# Power_USB.net
KiCad netlist of a schematic drawn in Altium Designer
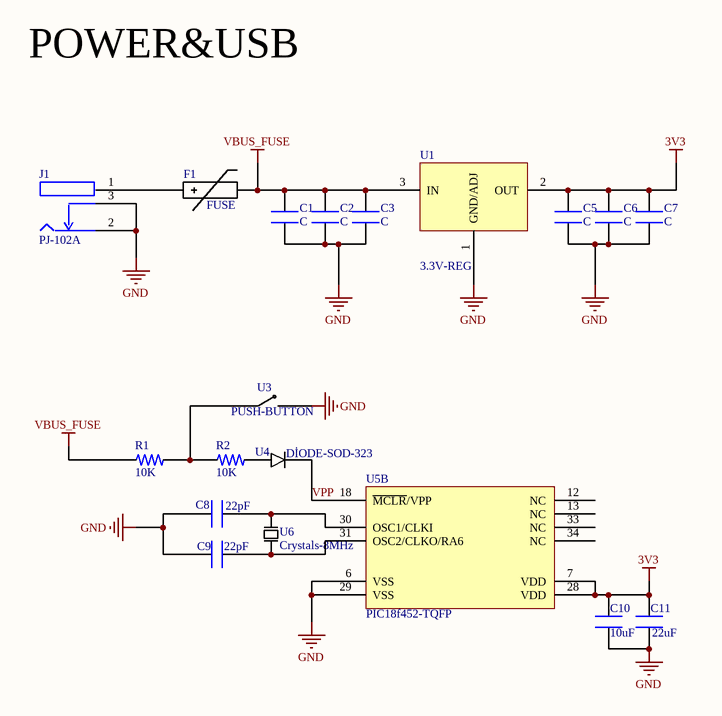
[diagram p0: Power&USB.SchDoc]

(export (version "E")
  (design (tool "Eeschema 10.0.6"))
  (components
    (comp (ref "C1")
      (value "C")
      (footprint "capacitor-1206:PCBComponent_1")
      (libsource (lib "capacitor-1206") (part "1206-CAPACİTOR"))
    )
    (comp (ref "C2")
      (value "C")
      (footprint "capacitor-1206:PCBComponent_1")
      (libsource (lib "capacitor-1206") (part "1206-CAPACİTOR"))
    )
    (comp (ref "C3")
      (value "C")
      (footprint "capacitor-1206:PCBComponent_1")
      (libsource (lib "capacitor-1206") (part "1206-CAPACİTOR"))
    )
    (comp (ref "C5")
      (value "C")
      (footprint "capacitor-1206:PCBComponent_1")
      (libsource (lib "capacitor-1206") (part "1206-CAPACİTOR"))
    )
    (comp (ref "C6")
      (value "C")
      (footprint "capacitor-1206:PCBComponent_1")
      (libsource (lib "capacitor-1206") (part "1206-CAPACİTOR"))
    )
    (comp (ref "C7")
      (value "C")
      (footprint "capacitor-1206:PCBComponent_1")
      (libsource (lib "capacitor-1206") (part "1206-CAPACİTOR"))
    )
    (comp (ref "C8")
      (value "22pF")
      (footprint "capacitor-1206:PCBComponent_1")
      (libsource (lib "capacitor-1206") (part "1206-CAPACİTOR"))
    )
    (comp (ref "C9")
      (value "22pF")
      (footprint "capacitor-1206:PCBComponent_1")
      (libsource (lib "capacitor-1206") (part "1206-CAPACİTOR"))
    )
    (comp (ref "C10")
      (value "10uF")
      (footprint "capacitor-1206:PCBComponent_1")
      (libsource (lib "capacitor-1206") (part "1206-CAPACİTOR"))
    )
    (comp (ref "C11")
      (value "22uF")
      (footprint "capacitor-1206:PCBComponent_1")
      (libsource (lib "capacitor-1206") (part "1206-CAPACİTOR"))
    )
    (comp (ref "F1")
      (value "FUSE")
      (footprint "Fuse-0805:PCBComponent_1")
      (libsource (lib "Fuse-0805") (part "Component_1"))
    )
    (comp (ref "J1")
      (value "PJ-102A")
      (footprint "FP-PJ-102A-MFG")
      (description "CONN PWR JACK 2X5.5MM SOLDER")
      (fields (field (name "MANUFACTURER") "CUI") (field (name "VOLTAGE") "24V"))
      (libsource (lib "Altium Content Vault") (part "0685d7ee7311ef3291d1b1b03391b7d"))
    )
    (comp (ref "R1")
      (value "10K")
      (footprint "1206-Resistor:PCBComponent_1")
      (libsource (lib "1206-Resistor") (part "1206-RESİSTOR"))
    )
    (comp (ref "R2")
      (value "10K")
      (footprint "1206-Resistor:PCBComponent_1")
      (libsource (lib "1206-Resistor") (part "1206-RESİSTOR"))
    )
    (comp (ref "U1")
      (value "3.3V-REG")
      (footprint "3.3V-VOLTAGEREG:PCBComponent_1")
      (libsource (lib "3.3V-VOLTAGEREG") (part "LD1117AG-33-AA3-A-R"))
    )
    (comp (ref "U3")
      (value "PUSH-BUTTON")
      (footprint "Button:PCBComponent_1")
      (libsource (lib "Button") (part "DS1042-03-2-1-KKA-160-10"))
    )
    (comp (ref "U4")
      (value "DİODE-SOD-323")
      (footprint "DİODE-SOD-323:PCBComponent_1")
      (libsource (lib "Diode-SOD-323") (part "1N4148WS-HT"))
    )
    (comp (ref "U5")
      (value "PIC18f452-TQFP")
      (footprint "pic16f1937:PCBComponent_1")
      (libsource (lib "dspic30f2023") (part "PIC18f452-TQFP"))
    )
    (comp (ref "U6")
      (value "Crystals-8MHz")
      (footprint "Crystals-8MHz:PCBComponent_1")
      (libsource (lib "Crystals-8MHz") (part "Crystals-8MHz-SMD"))
    )
  )
  (nets
    (net (code "1") (name "/VPP") (class "Default")
      (node (ref "U4") (pin "2") (pintype "passive"))
      (node (ref "U5") (pin "18") (pinfunction "~{MCLR}/VPP_18") (pintype "passive"))
    )
    (net (code "2") (name "3V3") (class "Default")
      (node (ref "C10") (pin "2") (pinfunction "2_2") (pintype "passive"))
      (node (ref "C11") (pin "2") (pinfunction "2_2") (pintype "passive"))
      (node (ref "C5") (pin "2") (pinfunction "2_2") (pintype "passive"))
      (node (ref "C6") (pin "2") (pinfunction "2_2") (pintype "passive"))
      (node (ref "C7") (pin "2") (pinfunction "2_2") (pintype "passive"))
      (node (ref "U1") (pin "2") (pinfunction "OUT_2") (pintype "passive"))
      (node (ref "U5") (pin "28") (pinfunction "VDD_28") (pintype "passive"))
      (node (ref "U5") (pin "7") (pinfunction "VDD_7") (pintype "passive"))
    )
    (net (code "3") (name "GND") (class "Default")
      (node (ref "C1") (pin "1") (pinfunction "1_1") (pintype "passive"))
      (node (ref "C10") (pin "1") (pinfunction "1_1") (pintype "passive"))
      (node (ref "C11") (pin "1") (pinfunction "1_1") (pintype "passive"))
      (node (ref "C2") (pin "1") (pinfunction "1_1") (pintype "passive"))
      (node (ref "C3") (pin "1") (pinfunction "1_1") (pintype "passive"))
      (node (ref "C5") (pin "1") (pinfunction "1_1") (pintype "passive"))
      (node (ref "C6") (pin "1") (pinfunction "1_1") (pintype "passive"))
      (node (ref "C7") (pin "1") (pinfunction "1_1") (pintype "passive"))
      (node (ref "C8") (pin "2") (pinfunction "2_2") (pintype "passive"))
      (node (ref "C9") (pin "2") (pinfunction "2_2") (pintype "passive"))
      (node (ref "J1") (pin "2") (pinfunction "2_2") (pintype "passive"))
      (node (ref "J1") (pin "3") (pinfunction "3_3") (pintype "passive"))
      (node (ref "U1") (pin "1") (pinfunction "GND/ADJ_1") (pintype "passive"))
      (node (ref "U3") (pin "2") (pintype "passive"))
      (node (ref "U5") (pin "29") (pinfunction "VSS_29") (pintype "passive"))
      (node (ref "U5") (pin "6") (pinfunction "VSS_6") (pintype "passive"))
    )
    (net (code "4") (name "Net-(F1-Pad8)") (class "Default")
      (node (ref "F1") (pin "8") (pintype "passive"))
      (node (ref "J1") (pin "1") (pinfunction "1_1") (pintype "passive"))
    )
    (net (code "5") (name "Net-(R1-Pad2)") (class "Default")
      (node (ref "R1") (pin "2") (pinfunction "2_2") (pintype "passive"))
      (node (ref "R2") (pin "1") (pinfunction "1_1") (pintype "passive"))
      (node (ref "U3") (pin "1") (pintype "passive"))
    )
    (net (code "6") (name "Net-(R2-Pad2)") (class "Default")
      (node (ref "R2") (pin "2") (pinfunction "2_2") (pintype "passive"))
      (node (ref "U4") (pin "1") (pintype "passive"))
    )
    (net (code "7") (name "Net-(U5B-OSC1{slash}CLKI)") (class "Default")
      (node (ref "C8") (pin "1") (pinfunction "1_1") (pintype "passive"))
      (node (ref "U5") (pin "30") (pinfunction "OSC1/CLKI_30") (pintype "passive"))
      (node (ref "U6") (pin "2") (pintype "passive"))
    )
    (net (code "8") (name "Net-(U5B-OSC2{slash}CLKO{slash}RA6)") (class "Default")
      (node (ref "C9") (pin "1") (pinfunction "1_1") (pintype "passive"))
      (node (ref "U5") (pin "31") (pinfunction "OSC2/CLKO/RA6_31") (pintype "passive"))
      (node (ref "U6") (pin "1") (pintype "passive"))
    )
    (net (code "9") (name "VBUS_FUSE") (class "Default")
      (node (ref "C1") (pin "2") (pinfunction "2_2") (pintype "passive"))
      (node (ref "C2") (pin "2") (pinfunction "2_2") (pintype "passive"))
      (node (ref "C3") (pin "2") (pinfunction "2_2") (pintype "passive"))
      (node (ref "F1") (pin "9") (pintype "passive"))
      (node (ref "R1") (pin "1") (pinfunction "1_1") (pintype "passive"))
      (node (ref "U1") (pin "3") (pinfunction "IN_3") (pintype "passive"))
    )
    (net (code "10") (name "unconnected-(U5B-NC-Pad12)") (class "Default")
      (node (ref "U5") (pin "12") (pinfunction "NC_12") (pintype "passive"))
    )
    (net (code "11") (name "unconnected-(U5B-NC-Pad13)") (class "Default")
      (node (ref "U5") (pin "13") (pinfunction "NC_13") (pintype "passive"))
    )
    (net (code "12") (name "unconnected-(U5B-NC-Pad33)") (class "Default")
      (node (ref "U5") (pin "33") (pinfunction "NC_33") (pintype "passive"))
    )
    (net (code "13") (name "unconnected-(U5B-NC-Pad34)") (class "Default")
      (node (ref "U5") (pin "34") (pinfunction "NC_34") (pintype "passive"))
    )
  )
)
